# I2C_Spilter_Board.net
KiCad netlist of a schematic drawn in EAGLE
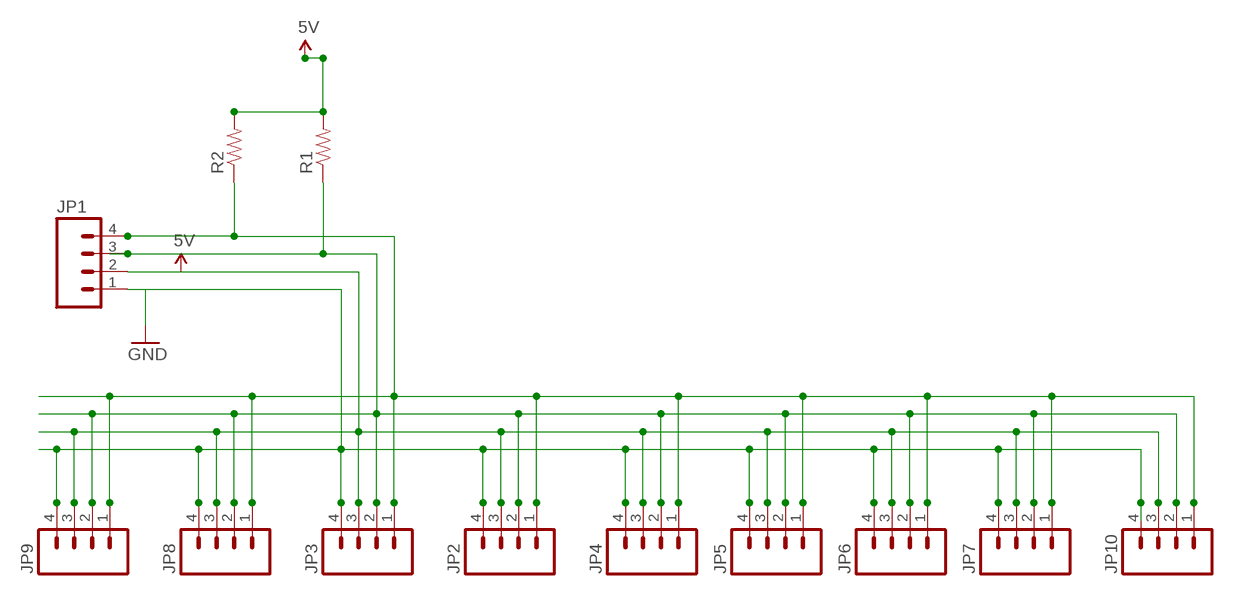
[diagram p0: schematic, sheet 1]

(export (version "E")
  (design (tool "Eeschema 10.0.6"))
  (components
    (comp (ref "JP1")
      (value "M04PTH")
      (footprint "eagle-import:1X04")
      (libsource (lib "eagle-import") (part "M04PTH"))
    )
    (comp (ref "JP2")
      (value "M04PTH")
      (footprint "eagle-import:1X04")
      (libsource (lib "eagle-import") (part "M04PTH"))
    )
    (comp (ref "JP3")
      (value "M04PTH")
      (footprint "eagle-import:1X04")
      (libsource (lib "eagle-import") (part "M04PTH"))
    )
    (comp (ref "JP4")
      (value "M04PTH")
      (footprint "eagle-import:1X04")
      (libsource (lib "eagle-import") (part "M04PTH"))
    )
    (comp (ref "JP5")
      (value "M04PTH")
      (footprint "eagle-import:1X04")
      (libsource (lib "eagle-import") (part "M04PTH"))
    )
    (comp (ref "JP6")
      (value "M04PTH")
      (footprint "eagle-import:1X04")
      (libsource (lib "eagle-import") (part "M04PTH"))
    )
    (comp (ref "JP7")
      (value "M04PTH")
      (footprint "eagle-import:1X04")
      (libsource (lib "eagle-import") (part "M04PTH"))
    )
    (comp (ref "JP8")
      (value "M04PTH")
      (footprint "eagle-import:1X04")
      (libsource (lib "eagle-import") (part "M04PTH"))
    )
    (comp (ref "JP9")
      (value "M04PTH")
      (footprint "eagle-import:1X04")
      (libsource (lib "eagle-import") (part "M04PTH"))
    )
    (comp (ref "JP10")
      (value "M04PTH")
      (footprint "eagle-import:1X04")
      (libsource (lib "eagle-import") (part "M04PTH"))
    )
    (comp (ref "R1")
      (value "RESISTORAXIAL-0.3")
      (footprint "eagle-import:AXIAL-0.3")
      (libsource (lib "eagle-import") (part "RESISTORAXIAL-0.3"))
    )
    (comp (ref "R2")
      (value "RESISTORAXIAL-0.3")
      (footprint "eagle-import:AXIAL-0.3")
      (libsource (lib "eagle-import") (part "RESISTORAXIAL-0.3"))
    )
  )
  (nets
    (net (code "1") (name "5V") (class "Default")
      (node (ref "JP1") (pin "2") (pinfunction "2_2") (pintype "passive"))
      (node (ref "JP10") (pin "3") (pinfunction "3_3") (pintype "passive"))
      (node (ref "JP2") (pin "3") (pinfunction "3_3") (pintype "passive"))
      (node (ref "JP3") (pin "3") (pinfunction "3_3") (pintype "passive"))
      (node (ref "JP4") (pin "3") (pinfunction "3_3") (pintype "passive"))
      (node (ref "JP5") (pin "3") (pinfunction "3_3") (pintype "passive"))
      (node (ref "JP6") (pin "3") (pinfunction "3_3") (pintype "passive"))
      (node (ref "JP7") (pin "3") (pinfunction "3_3") (pintype "passive"))
      (node (ref "JP8") (pin "3") (pinfunction "3_3") (pintype "passive"))
      (node (ref "JP9") (pin "3") (pinfunction "3_3") (pintype "passive"))
      (node (ref "R1") (pin "P$2") (pinfunction "2_P$2") (pintype "passive"))
      (node (ref "R2") (pin "P$2") (pinfunction "2_P$2") (pintype "passive"))
    )
    (net (code "2") (name "GND") (class "Default")
      (node (ref "JP1") (pin "1") (pinfunction "1_1") (pintype "passive"))
      (node (ref "JP10") (pin "4") (pinfunction "4_4") (pintype "passive"))
      (node (ref "JP2") (pin "4") (pinfunction "4_4") (pintype "passive"))
      (node (ref "JP3") (pin "4") (pinfunction "4_4") (pintype "passive"))
      (node (ref "JP4") (pin "4") (pinfunction "4_4") (pintype "passive"))
      (node (ref "JP5") (pin "4") (pinfunction "4_4") (pintype "passive"))
      (node (ref "JP6") (pin "4") (pinfunction "4_4") (pintype "passive"))
      (node (ref "JP7") (pin "4") (pinfunction "4_4") (pintype "passive"))
      (node (ref "JP8") (pin "4") (pinfunction "4_4") (pintype "passive"))
      (node (ref "JP9") (pin "4") (pinfunction "4_4") (pintype "passive"))
    )
    (net (code "3") (name "Net-(R1-1)") (class "Default")
      (node (ref "JP1") (pin "3") (pinfunction "3_3") (pintype "passive"))
      (node (ref "JP10") (pin "2") (pinfunction "2_2") (pintype "passive"))
      (node (ref "JP2") (pin "2") (pinfunction "2_2") (pintype "passive"))
      (node (ref "JP3") (pin "2") (pinfunction "2_2") (pintype "passive"))
      (node (ref "JP4") (pin "2") (pinfunction "2_2") (pintype "passive"))
      (node (ref "JP5") (pin "2") (pinfunction "2_2") (pintype "passive"))
      (node (ref "JP6") (pin "2") (pinfunction "2_2") (pintype "passive"))
      (node (ref "JP7") (pin "2") (pinfunction "2_2") (pintype "passive"))
      (node (ref "JP8") (pin "2") (pinfunction "2_2") (pintype "passive"))
      (node (ref "JP9") (pin "2") (pinfunction "2_2") (pintype "passive"))
      (node (ref "R1") (pin "P$1") (pinfunction "1_P$1") (pintype "passive"))
    )
    (net (code "4") (name "Net-(R2-1)") (class "Default")
      (node (ref "JP1") (pin "4") (pinfunction "4_4") (pintype "passive"))
      (node (ref "JP10") (pin "1") (pinfunction "1_1") (pintype "passive"))
      (node (ref "JP2") (pin "1") (pinfunction "1_1") (pintype "passive"))
      (node (ref "JP3") (pin "1") (pinfunction "1_1") (pintype "passive"))
      (node (ref "JP4") (pin "1") (pinfunction "1_1") (pintype "passive"))
      (node (ref "JP5") (pin "1") (pinfunction "1_1") (pintype "passive"))
      (node (ref "JP6") (pin "1") (pinfunction "1_1") (pintype "passive"))
      (node (ref "JP7") (pin "1") (pinfunction "1_1") (pintype "passive"))
      (node (ref "JP8") (pin "1") (pinfunction "1_1") (pintype "passive"))
      (node (ref "JP9") (pin "1") (pinfunction "1_1") (pintype "passive"))
      (node (ref "R2") (pin "P$1") (pinfunction "1_P$1") (pintype "passive"))
    )
  )
)
